# SCHEMATIC.net
KiCad netlist of a schematic drawn in Altium Designer
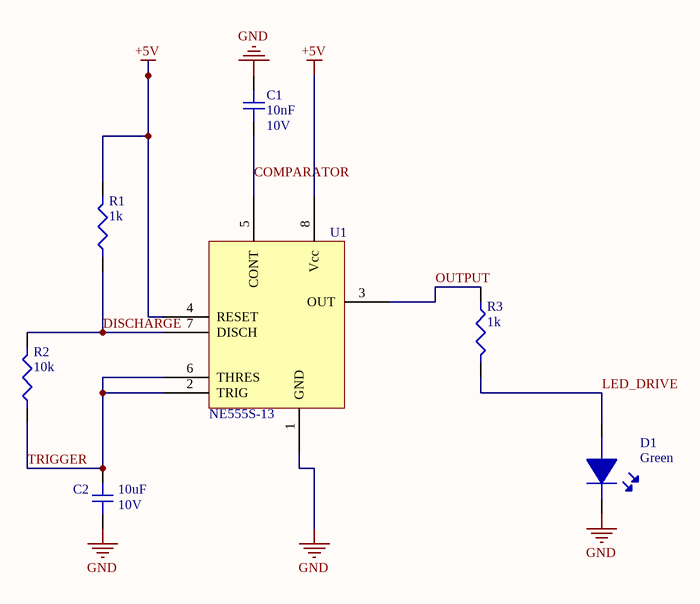
[diagram p0: SCHEMATIC.SchDoc]

(export (version "E")
  (design (tool "Eeschema 10.0.6"))
  (components
    (comp (ref "C1")
      (value "10nF")
      (footprint "C0603")
      (description "Cap Ceramic 0.01uF 10V X7R 10% SMD 0603 125C Paper T/R")
      (fields
        (field (name "MANUFACTURER") "Yageo")
        (field (name "MANUFACTURER PART NUMBER") "CC0603KRX7R6BB103")
        (field (name "VOLTAGE RATING") "10V")
      )
      (libsource (lib "SCH_LIB_andrei") (part "CC0603KRX7R6BB103"))
    )
    (comp (ref "C2")
      (value "10uF")
      (footprint "C0603")
      (description "Cap Ceramic 10uF 10V X5R 10% SMD 0603 85C Paper T/R")
      (fields
        (field (name "MANUFACTURER") "Murata")
        (field (name "MANUFACTURER PART NUMBER") "GRM188R61A106KE69D")
        (field (name "VOLTAGE") "10V")
      )
      (libsource (lib "SCH_LIB_andrei") (part "GRM188R61A106KE69D"))
    )
    (comp (ref "D1")
      (value "Green")
      (footprint "LED_0603")
      (description "LED GREEN CLEAR 0603 SMD")
      (fields
        (field (name "MANUFACTURER") "Vishay Lite-On")
        (field (name "MANUFACTURER PART NUMBER") "LTST-C190GKT")
      )
      (libsource (lib "SCH_LIB_andrei") (part "LTST-C190GKT"))
    )
    (comp (ref "R1")
      (value "1k")
      (footprint "R0603")
      (description "RES SMD 1K OHM 5% 1/4W 0603")
      (fields (field (name "MANUFACTURER") "Rohm") (field (name "MANUFACTURER PART NUMBER") "ESR03EZPJ102"))
      (libsource (lib "SCH_LIB_andrei") (part "ESR03EZPJ102"))
    )
    (comp (ref "R2")
      (value "10k")
      (footprint "R0603")
      (description "RES SMD 10K OHM 0.5% 1/16W 0816")
      (fields
        (field (name "MANUFACTURER") "Susumu")
        (field (name "MANUFACTURER PART NUMBER") "RR0816P-103-D")
      )
      (libsource (lib "SCH_LIB_andrei") (part "RR0816P-103-D"))
    )
    (comp (ref "R3")
      (value "1k")
      (footprint "R0603")
      (description "RES SMD 1K OHM 5% 1/4W 0603")
      (fields (field (name "MANUFACTURER") "Rohm") (field (name "MANUFACTURER PART NUMBER") "ESR03EZPJ102"))
      (libsource (lib "SCH_LIB_andrei") (part "ESR03EZPJ102"))
    )
    (comp (ref "U1")
      (value "NE555S-13")
      (footprint "SOIC8")
      (description "555 Type, Timer/Oscillator (Single) IC 500kHz 8-SOIC (0.154\", 3.90mm Width)")
      (fields (field (name "MANUFACTURER") "Diodes"))
      (libsource (lib "SCH_LIB_andrei") (part "NE555S-13"))
    )
  )
  (nets
    (net (code "1") (name "+5V") (class "Default")
      (node (ref "R1") (pin "2") (pinfunction "2_2") (pintype "passive"))
      (node (ref "U1") (pin "4") (pinfunction "RESET_4") (pintype "passive"))
      (node (ref "U1") (pin "8") (pinfunction "Vcc_8") (pintype "passive"))
    )
    (net (code "2") (name "/COMPARATOR") (class "Default")
      (node (ref "C1") (pin "1") (pinfunction "1_1") (pintype "passive"))
      (node (ref "U1") (pin "5") (pinfunction "CONT_5") (pintype "passive"))
    )
    (net (code "3") (name "/DISCHARGE") (class "Default")
      (node (ref "R1") (pin "1") (pinfunction "1_1") (pintype "passive"))
      (node (ref "R2") (pin "2") (pinfunction "2_2") (pintype "passive"))
      (node (ref "U1") (pin "7") (pinfunction "DISCH_7") (pintype "passive"))
    )
    (net (code "4") (name "/LED_DRIVE") (class "Default")
      (node (ref "D1") (pin "1") (pinfunction "1_1") (pintype "passive"))
      (node (ref "R3") (pin "2") (pinfunction "2_2") (pintype "passive"))
    )
    (net (code "5") (name "/OUTPUT") (class "Default")
      (node (ref "R3") (pin "1") (pinfunction "1_1") (pintype "passive"))
      (node (ref "U1") (pin "3") (pinfunction "OUT_3") (pintype "passive"))
    )
    (net (code "6") (name "/TRIGGER") (class "Default")
      (node (ref "C2") (pin "1") (pinfunction "1_1") (pintype "passive"))
      (node (ref "R2") (pin "1") (pinfunction "1_1") (pintype "passive"))
      (node (ref "U1") (pin "2") (pinfunction "TRIG_2") (pintype "passive"))
      (node (ref "U1") (pin "6") (pinfunction "THRES_6") (pintype "passive"))
    )
    (net (code "7") (name "GND") (class "Default")
      (node (ref "C1") (pin "2") (pinfunction "2_2") (pintype "passive"))
      (node (ref "C2") (pin "2") (pinfunction "2_2") (pintype "passive"))
      (node (ref "D1") (pin "2") (pinfunction "2_2") (pintype "passive"))
      (node (ref "U1") (pin "1") (pinfunction "GND_1") (pintype "passive"))
    )
  )
)
